# SampleANDHold.net
KiCad netlist of a schematic drawn in Altium Designer
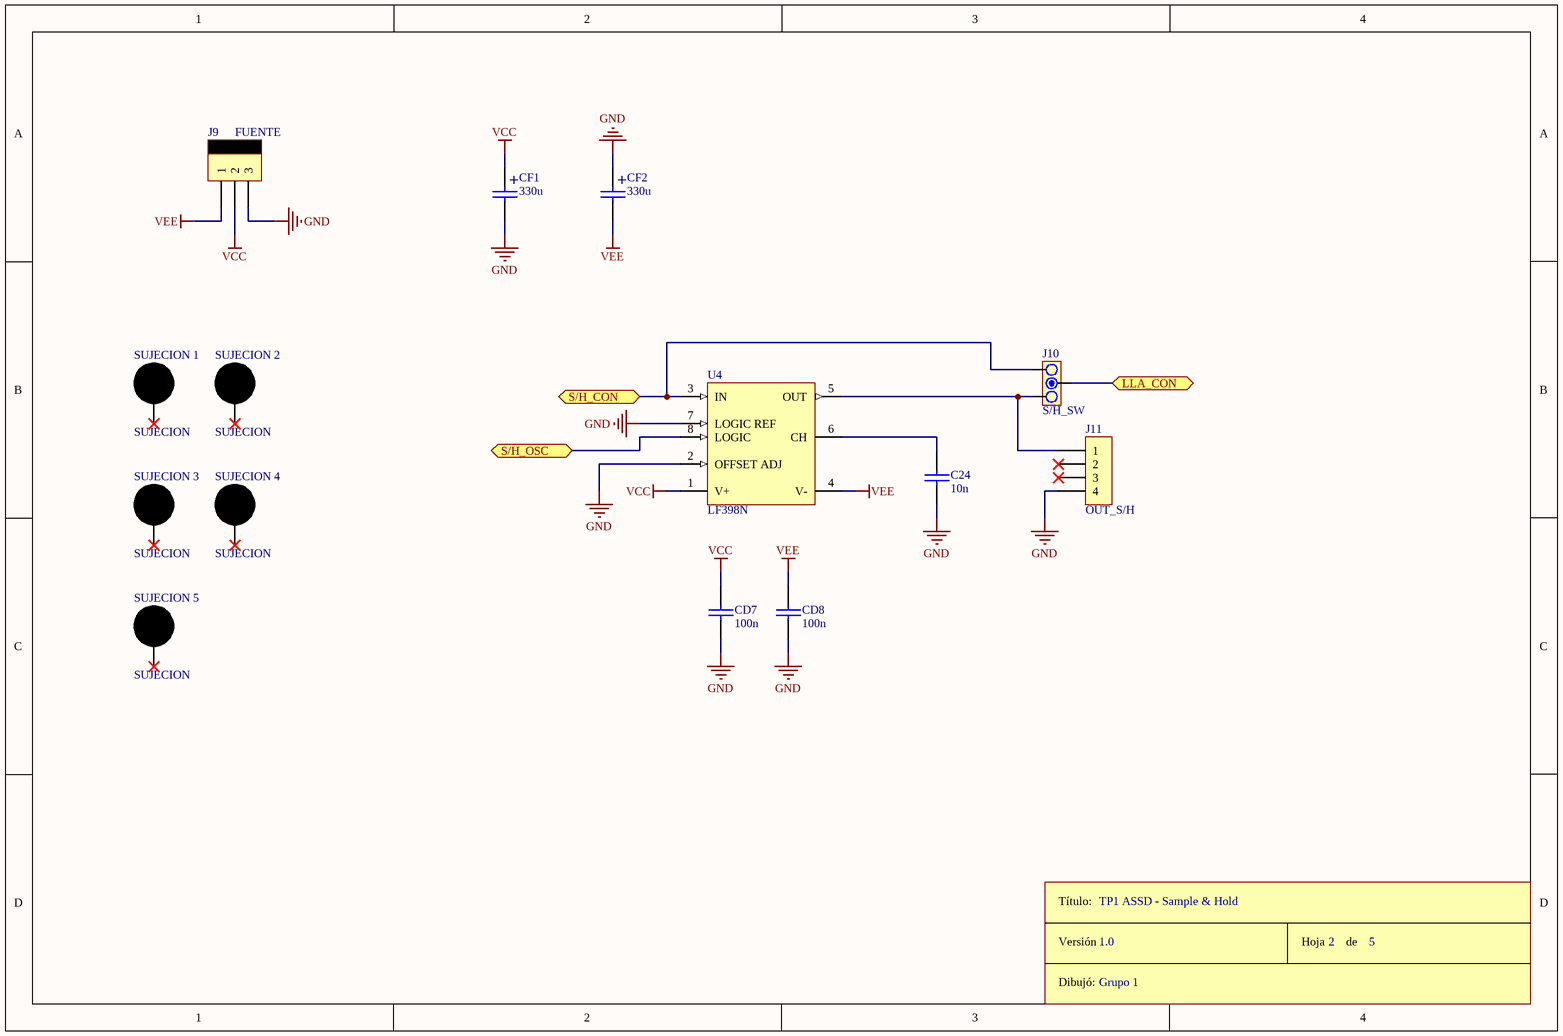
[diagram p0: SampleANDHold.SchDoc]

(export (version "E")
  (design (tool "Eeschema 10.0.6"))
  (components
    (comp (ref "C24") (value "10n") (footprint "CAP100") (libsource (lib "LIBEBAL") (part "CAP")))
    (comp (ref "CD7") (value "100n") (footprint "CAP100") (libsource (lib "LIBEBAL") (part "CAP")))
    (comp (ref "CD8") (value "100n") (footprint "CAP100") (libsource (lib "LIBEBAL") (part "CAP")))
    (comp (ref "CF1") (value "330u") (footprint "CAP200RP") (libsource (lib "LIBEBAL") (part "CAPPOL")))
    (comp (ref "CF2") (value "330u") (footprint "CAP200RP") (libsource (lib "LIBEBAL") (part "CAPPOL")))
    (comp (ref "J9") (value "FUENTE") (footprint "MOLEX3") (libsource (lib "LIBEBAL") (part "MOLEX3")))
    (comp (ref "J10") (value "S/H_SW") (footprint "JUMPER3") (libsource (lib "LIBEBAL") (part "JUMPER3")))
    (comp (ref "J11") (value "OUT_S/H") (footprint "SIP4") (libsource (lib "LIBEBAL") (part "CON4")))
    (comp (ref "ROT2") (value "Rótulo") (libsource (lib "LIB PIO IX") (part "Rótulo")))
    (comp (ref "SUJECION 1")
      (value "SUJECION")
      (footprint "SUJECION (5.00MM - 3.50MM)")
      (libsource (lib "LIB2013") (part "SUJECION"))
    )
    (comp (ref "SUJECION 2")
      (value "SUJECION")
      (footprint "SUJECION (5.00MM - 3.50MM)")
      (libsource (lib "LIB2013") (part "SUJECION"))
    )
    (comp (ref "SUJECION 3")
      (value "SUJECION")
      (footprint "SUJECION (5.00MM - 3.50MM)")
      (libsource (lib "LIB2013") (part "SUJECION"))
    )
    (comp (ref "SUJECION 4")
      (value "SUJECION")
      (footprint "SUJECION (5.00MM - 3.50MM)")
      (libsource (lib "LIB2013") (part "SUJECION"))
    )
    (comp (ref "SUJECION 5")
      (value "SUJECION")
      (footprint "SUJECION (5.00MM - 3.50MM)")
      (libsource (lib "LIB2013") (part "SUJECION"))
    )
    (comp (ref "U4")
      (value "LF398N")
      (footprint "N08E")
      (description "Monolithic Sample-and-Hold Circuits")
      (fields
        (field (name "MANUFACTURER") "National Semiconductor")
        (field (name "DIGIKEYPARTNUMBER") "LF398N-ND")
        (field (name "PUBLISHER") "Altium Limited")
      )
      (libsource (lib "NSC Analog") (part "LF398N"))
    )
  )
  (nets
    (net (code "1") (name "/LLA_CON") (class "Default")
      (node (ref "J10") (pin "2") (pinfunction "2_2") (pintype "passive"))
    )
    (net (code "2") (name "/S{slash}H_CON") (class "Default")
      (node (ref "J10") (pin "3") (pinfunction "3_3") (pintype "passive"))
      (node (ref "U4") (pin "3") (pinfunction "IN_3") (pintype "input"))
    )
    (net (code "3") (name "/S{slash}H_OSC") (class "Default")
      (node (ref "U4") (pin "8") (pinfunction "LOGIC_8") (pintype "input"))
    )
    (net (code "4") (name "GND") (class "Default")
      (node (ref "C24") (pin "2") (pinfunction "2_2") (pintype "passive"))
      (node (ref "CD7") (pin "2") (pinfunction "2_2") (pintype "passive"))
      (node (ref "CD8") (pin "2") (pinfunction "2_2") (pintype "passive"))
      (node (ref "CF1") (pin "2") (pinfunction "2_2") (pintype "passive"))
      (node (ref "CF2") (pin "1") (pinfunction "1_1") (pintype "passive"))
      (node (ref "J11") (pin "4") (pinfunction "4_4") (pintype "passive"))
      (node (ref "J9") (pin "3") (pinfunction "3_3") (pintype "passive"))
      (node (ref "U4") (pin "2") (pinfunction "OFFSET_ADJ_2") (pintype "input"))
      (node (ref "U4") (pin "7") (pinfunction "LOGIC_REF_7") (pintype "input"))
    )
    (net (code "5") (name "Net-(U4-CH)") (class "Default")
      (node (ref "C24") (pin "1") (pinfunction "1_1") (pintype "passive"))
      (node (ref "U4") (pin "6") (pinfunction "CH_6") (pintype "passive"))
    )
    (net (code "6") (name "Net-(U4-OUT)") (class "Default")
      (node (ref "J10") (pin "1") (pinfunction "1_1") (pintype "passive"))
      (node (ref "J11") (pin "1") (pinfunction "1_1") (pintype "passive"))
      (node (ref "U4") (pin "5") (pinfunction "OUT_5") (pintype "output"))
    )
    (net (code "7") (name "VCC") (class "Default")
      (node (ref "CD7") (pin "1") (pinfunction "1_1") (pintype "passive"))
      (node (ref "CF1") (pin "1") (pinfunction "1_1") (pintype "passive"))
      (node (ref "J9") (pin "2") (pinfunction "2_2") (pintype "passive"))
      (node (ref "U4") (pin "1") (pinfunction "V+_1") (pintype "power_in"))
    )
    (net (code "8") (name "VEE") (class "Default")
      (node (ref "CD8") (pin "1") (pinfunction "1_1") (pintype "passive"))
      (node (ref "CF2") (pin "2") (pinfunction "2_2") (pintype "passive"))
      (node (ref "J9") (pin "1") (pinfunction "1_1") (pintype "passive"))
      (node (ref "U4") (pin "4") (pinfunction "V-_4") (pintype "power_in"))
    )
    (net (code "9") (name "unconnected-(J11-Pad2)") (class "Default")
      (node (ref "J11") (pin "2") (pinfunction "2_2") (pintype "passive+no_connect"))
    )
    (net (code "10") (name "unconnected-(J11-Pad3)") (class "Default")
      (node (ref "J11") (pin "3") (pinfunction "3_3") (pintype "passive+no_connect"))
    )
    (net (code "11") (name "unconnected-(SUJECION 1-Pad1)") (class "Default")
      (node (ref "SUJECION 1") (pin "1") (pinfunction "1_1") (pintype "passive+no_connect"))
    )
    (net (code "12") (name "unconnected-(SUJECION 2-Pad1)") (class "Default")
      (node (ref "SUJECION 2") (pin "1") (pinfunction "1_1") (pintype "passive+no_connect"))
    )
    (net (code "13") (name "unconnected-(SUJECION 3-Pad1)") (class "Default")
      (node (ref "SUJECION 3") (pin "1") (pinfunction "1_1") (pintype "passive+no_connect"))
    )
    (net (code "14") (name "unconnected-(SUJECION 4-Pad1)") (class "Default")
      (node (ref "SUJECION 4") (pin "1") (pinfunction "1_1") (pintype "passive+no_connect"))
    )
    (net (code "15") (name "unconnected-(SUJECION 5-Pad1)") (class "Default")
      (node (ref "SUJECION 5") (pin "1") (pinfunction "1_1") (pintype "passive+no_connect"))
    )
  )
)
